# Lab4_schematic.net
KiCad netlist of a schematic drawn in EAGLE
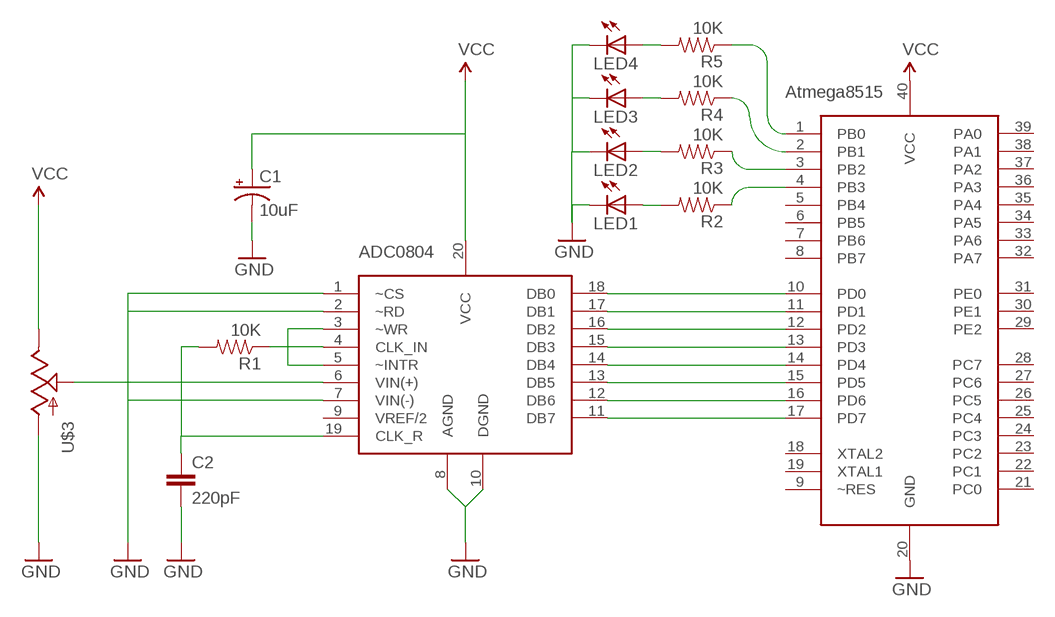
[diagram p0: schematic, sheet 1]

(export (version "E")
  (design (tool "Eeschema 10.0.6"))
  (components
    (comp (ref "C1")
      (value "10uF")
      (footprint "eagle-import:EIA3216")
      (libsource (lib "eagle-import") (part "CAP_POL1206"))
    )
    (comp (ref "C2")
      (value "220pF")
      (footprint "eagle-import:CAP-PTH-SMALL")
      (libsource (lib "eagle-import") (part "CAPPTH"))
    )
    (comp (ref "LED1")
      (value "LED3MM")
      (footprint "eagle-import:LED3MM")
      (libsource (lib "eagle-import") (part "LED3MM"))
    )
    (comp (ref "LED2")
      (value "LED3MM")
      (footprint "eagle-import:LED3MM")
      (libsource (lib "eagle-import") (part "LED3MM"))
    )
    (comp (ref "LED3")
      (value "LED3MM")
      (footprint "eagle-import:LED3MM")
      (libsource (lib "eagle-import") (part "LED3MM"))
    )
    (comp (ref "LED4")
      (value "LED3MM")
      (footprint "eagle-import:LED3MM")
      (libsource (lib "eagle-import") (part "LED3MM"))
    )
    (comp (ref "R1")
      (value "10K")
      (footprint "eagle-import:AXIAL-0.3")
      (libsource (lib "eagle-import") (part "RESISTORPTH1"))
    )
    (comp (ref "R2")
      (value "10K")
      (footprint "eagle-import:AXIAL-0.3")
      (libsource (lib "eagle-import") (part "RESISTORPTH1"))
    )
    (comp (ref "R3")
      (value "10K")
      (footprint "eagle-import:AXIAL-0.3")
      (libsource (lib "eagle-import") (part "RESISTORPTH1"))
    )
    (comp (ref "R4")
      (value "10K")
      (footprint "eagle-import:AXIAL-0.3")
      (libsource (lib "eagle-import") (part "RESISTORPTH1"))
    )
    (comp (ref "R5")
      (value "10K")
      (footprint "eagle-import:AXIAL-0.3")
      (libsource (lib "eagle-import") (part "RESISTORPTH1"))
    )
    (comp (ref "U$1")
      (value "ATMEGA8515")
      (footprint "eagle-import:DIL-40")
      (libsource (lib "eagle-import") (part "ATMEGA8515"))
    )
    (comp (ref "U$2")
      (value "ADC0804")
      (footprint "eagle-import:DIL20")
      (libsource (lib "eagle-import") (part "ADC0804"))
    )
    (comp (ref "U$3")
      (value "POT")
      (footprint "eagle-import:ALPS_POT")
      (libsource (lib "eagle-import") (part "POT"))
    )
  )
  (nets
    (net (code "1") (name "GND") (class "Default")
      (node (ref "C1") (pin "C") (pinfunction "-_C") (pintype "passive"))
      (node (ref "C2") (pin "2") (pinfunction "2_2") (pintype "passive"))
      (node (ref "LED1") (pin "K") (pinfunction "C_K") (pintype "passive"))
      (node (ref "LED2") (pin "K") (pinfunction "C_K") (pintype "passive"))
      (node (ref "LED3") (pin "K") (pinfunction "C_K") (pintype "passive"))
      (node (ref "LED4") (pin "K") (pinfunction "C_K") (pintype "passive"))
      (node (ref "U$1") (pin "20") (pinfunction "GND_20") (pintype "bidirectional"))
      (node (ref "U$2") (pin "1") (pinfunction "~{CS}_1") (pintype "bidirectional"))
      (node (ref "U$2") (pin "10") (pinfunction "DGND_10") (pintype "bidirectional"))
      (node (ref "U$2") (pin "2") (pinfunction "~{RD}_2") (pintype "bidirectional"))
      (node (ref "U$2") (pin "7") (pinfunction "VIN(-)_7") (pintype "bidirectional"))
      (node (ref "U$2") (pin "8") (pinfunction "AGND_8") (pintype "bidirectional"))
      (node (ref "U$3") (pin "P$3") (pinfunction "A_P$3") (pintype "passive"))
    )
    (net (code "2") (name "Net-(R1-1)") (class "Default")
      (node (ref "R1") (pin "P$1") (pinfunction "1_P$1") (pintype "passive"))
      (node (ref "U$2") (pin "4") (pinfunction "CLK_IN_4") (pintype "bidirectional"))
    )
    (net (code "3") (name "Net-(R1-2)") (class "Default")
      (node (ref "C2") (pin "1") (pinfunction "1_1") (pintype "passive"))
      (node (ref "R1") (pin "P$2") (pinfunction "2_P$2") (pintype "passive"))
      (node (ref "U$2") (pin "19") (pinfunction "CLK_R_19") (pintype "bidirectional"))
    )
    (net (code "4") (name "Net-(R2-1)") (class "Default")
      (node (ref "R2") (pin "P$1") (pinfunction "1_P$1") (pintype "passive"))
      (node (ref "U$1") (pin "4") (pinfunction "PB3_4") (pintype "bidirectional"))
    )
    (net (code "5") (name "Net-(R2-2)") (class "Default")
      (node (ref "LED1") (pin "A") (pinfunction "A_A") (pintype "passive"))
      (node (ref "R2") (pin "P$2") (pinfunction "2_P$2") (pintype "passive"))
    )
    (net (code "6") (name "Net-(R3-1)") (class "Default")
      (node (ref "R3") (pin "P$1") (pinfunction "1_P$1") (pintype "passive"))
      (node (ref "U$1") (pin "3") (pinfunction "PB2_3") (pintype "bidirectional"))
    )
    (net (code "7") (name "Net-(R3-2)") (class "Default")
      (node (ref "LED2") (pin "A") (pinfunction "A_A") (pintype "passive"))
      (node (ref "R3") (pin "P$2") (pinfunction "2_P$2") (pintype "passive"))
    )
    (net (code "8") (name "Net-(R4-1)") (class "Default")
      (node (ref "R4") (pin "P$1") (pinfunction "1_P$1") (pintype "passive"))
      (node (ref "U$1") (pin "2") (pinfunction "PB1_2") (pintype "bidirectional"))
    )
    (net (code "9") (name "Net-(R4-2)") (class "Default")
      (node (ref "LED3") (pin "A") (pinfunction "A_A") (pintype "passive"))
      (node (ref "R4") (pin "P$2") (pinfunction "2_P$2") (pintype "passive"))
    )
    (net (code "10") (name "Net-(R5-1)") (class "Default")
      (node (ref "R5") (pin "P$1") (pinfunction "1_P$1") (pintype "passive"))
      (node (ref "U$1") (pin "1") (pinfunction "PB0_1") (pintype "bidirectional"))
    )
    (net (code "11") (name "Net-(R5-2)") (class "Default")
      (node (ref "LED4") (pin "A") (pinfunction "A_A") (pintype "passive"))
      (node (ref "R5") (pin "P$2") (pinfunction "2_P$2") (pintype "passive"))
    )
    (net (code "12") (name "Net-(U$1-PD0)") (class "Default")
      (node (ref "U$1") (pin "10") (pinfunction "PD0_10") (pintype "bidirectional"))
      (node (ref "U$2") (pin "18") (pinfunction "DB0_18") (pintype "bidirectional"))
    )
    (net (code "13") (name "Net-(U$1-PD1)") (class "Default")
      (node (ref "U$1") (pin "11") (pinfunction "PD1_11") (pintype "bidirectional"))
      (node (ref "U$2") (pin "17") (pinfunction "DB1_17") (pintype "bidirectional"))
    )
    (net (code "14") (name "Net-(U$1-PD2)") (class "Default")
      (node (ref "U$1") (pin "12") (pinfunction "PD2_12") (pintype "bidirectional"))
      (node (ref "U$2") (pin "16") (pinfunction "DB2_16") (pintype "bidirectional"))
    )
    (net (code "15") (name "Net-(U$1-PD3)") (class "Default")
      (node (ref "U$1") (pin "13") (pinfunction "PD3_13") (pintype "bidirectional"))
      (node (ref "U$2") (pin "15") (pinfunction "DB3_15") (pintype "bidirectional"))
    )
    (net (code "16") (name "Net-(U$1-PD4)") (class "Default")
      (node (ref "U$1") (pin "14") (pinfunction "PD4_14") (pintype "bidirectional"))
      (node (ref "U$2") (pin "14") (pinfunction "DB4_14") (pintype "bidirectional"))
    )
    (net (code "17") (name "Net-(U$1-PD5)") (class "Default")
      (node (ref "U$1") (pin "15") (pinfunction "PD5_15") (pintype "bidirectional"))
      (node (ref "U$2") (pin "13") (pinfunction "DB5_13") (pintype "bidirectional"))
    )
    (net (code "18") (name "Net-(U$1-PD6)") (class "Default")
      (node (ref "U$1") (pin "16") (pinfunction "PD6_16") (pintype "bidirectional"))
      (node (ref "U$2") (pin "12") (pinfunction "DB6_12") (pintype "bidirectional"))
    )
    (net (code "19") (name "Net-(U$1-PD7)") (class "Default")
      (node (ref "U$1") (pin "17") (pinfunction "PD7_17") (pintype "bidirectional"))
      (node (ref "U$2") (pin "11") (pinfunction "DB7_11") (pintype "bidirectional"))
    )
    (net (code "20") (name "Net-(U$2-VIN(+))") (class "Default")
      (node (ref "U$2") (pin "6") (pinfunction "VIN(+)_6") (pintype "bidirectional"))
      (node (ref "U$3") (pin "P$2") (pinfunction "S_P$2") (pintype "passive"))
    )
    (net (code "21") (name "Net-(U$2-~{INTR})") (class "Default")
      (node (ref "U$2") (pin "3") (pinfunction "~{WR}_3") (pintype "bidirectional"))
      (node (ref "U$2") (pin "5") (pinfunction "~{INTR}_5") (pintype "bidirectional"))
    )
    (net (code "22") (name "VCC") (class "Default")
      (node (ref "C1") (pin "A") (pinfunction "+_A") (pintype "passive"))
      (node (ref "U$1") (pin "40") (pinfunction "VCC_40") (pintype "bidirectional"))
      (node (ref "U$2") (pin "20") (pinfunction "VCC_20") (pintype "bidirectional"))
      (node (ref "U$3") (pin "P$1") (pinfunction "E_P$1") (pintype "passive"))
    )
    (net (code "23") (name "unconnected-(U$1-PA0-Pad39)") (class "Default")
      (node (ref "U$1") (pin "39") (pinfunction "PA0_39") (pintype "bidirectional"))
    )
    (net (code "24") (name "unconnected-(U$1-PA1-Pad38)") (class "Default")
      (node (ref "U$1") (pin "38") (pinfunction "PA1_38") (pintype "bidirectional"))
    )
    (net (code "25") (name "unconnected-(U$1-PA2-Pad37)") (class "Default")
      (node (ref "U$1") (pin "37") (pinfunction "PA2_37") (pintype "bidirectional"))
    )
    (net (code "26") (name "unconnected-(U$1-PA3-Pad36)") (class "Default")
      (node (ref "U$1") (pin "36") (pinfunction "PA3_36") (pintype "bidirectional"))
    )
    (net (code "27") (name "unconnected-(U$1-PA4-Pad35)") (class "Default")
      (node (ref "U$1") (pin "35") (pinfunction "PA4_35") (pintype "bidirectional"))
    )
    (net (code "28") (name "unconnected-(U$1-PA5-Pad34)") (class "Default")
      (node (ref "U$1") (pin "34") (pinfunction "PA5_34") (pintype "bidirectional"))
    )
    (net (code "29") (name "unconnected-(U$1-PA6-Pad33)") (class "Default")
      (node (ref "U$1") (pin "33") (pinfunction "PA6_33") (pintype "bidirectional"))
    )
    (net (code "30") (name "unconnected-(U$1-PA7-Pad32)") (class "Default")
      (node (ref "U$1") (pin "32") (pinfunction "PA7_32") (pintype "bidirectional"))
    )
    (net (code "31") (name "unconnected-(U$1-PB4-Pad5)") (class "Default")
      (node (ref "U$1") (pin "5") (pinfunction "PB4_5") (pintype "bidirectional"))
    )
    (net (code "32") (name "unconnected-(U$1-PB5-Pad6)") (class "Default")
      (node (ref "U$1") (pin "6") (pinfunction "PB5_6") (pintype "bidirectional"))
    )
    (net (code "33") (name "unconnected-(U$1-PB6-Pad7)") (class "Default")
      (node (ref "U$1") (pin "7") (pinfunction "PB6_7") (pintype "bidirectional"))
    )
    (net (code "34") (name "unconnected-(U$1-PB7-Pad8)") (class "Default")
      (node (ref "U$1") (pin "8") (pinfunction "PB7_8") (pintype "bidirectional"))
    )
    (net (code "35") (name "unconnected-(U$1-PC0-Pad21)") (class "Default")
      (node (ref "U$1") (pin "21") (pinfunction "PC0_21") (pintype "bidirectional"))
    )
    (net (code "36") (name "unconnected-(U$1-PC1-Pad22)") (class "Default")
      (node (ref "U$1") (pin "22") (pinfunction "PC1_22") (pintype "bidirectional"))
    )
    (net (code "37") (name "unconnected-(U$1-PC2-Pad23)") (class "Default")
      (node (ref "U$1") (pin "23") (pinfunction "PC2_23") (pintype "bidirectional"))
    )
    (net (code "38") (name "unconnected-(U$1-PC3-Pad24)") (class "Default")
      (node (ref "U$1") (pin "24") (pinfunction "PC3_24") (pintype "bidirectional"))
    )
    (net (code "39") (name "unconnected-(U$1-PC4-Pad25)") (class "Default")
      (node (ref "U$1") (pin "25") (pinfunction "PC4_25") (pintype "bidirectional"))
    )
    (net (code "40") (name "unconnected-(U$1-PC5-Pad26)") (class "Default")
      (node (ref "U$1") (pin "26") (pinfunction "PC5_26") (pintype "bidirectional"))
    )
    (net (code "41") (name "unconnected-(U$1-PC6-Pad27)") (class "Default")
      (node (ref "U$1") (pin "27") (pinfunction "PC6_27") (pintype "bidirectional"))
    )
    (net (code "42") (name "unconnected-(U$1-PC7-Pad28)") (class "Default")
      (node (ref "U$1") (pin "28") (pinfunction "PC7_28") (pintype "bidirectional"))
    )
    (net (code "43") (name "unconnected-(U$1-PE0-Pad31)") (class "Default")
      (node (ref "U$1") (pin "31") (pinfunction "PE0_31") (pintype "bidirectional"))
    )
    (net (code "44") (name "unconnected-(U$1-PE1-Pad30)") (class "Default")
      (node (ref "U$1") (pin "30") (pinfunction "PE1_30") (pintype "bidirectional"))
    )
    (net (code "45") (name "unconnected-(U$1-PE2-Pad29)") (class "Default")
      (node (ref "U$1") (pin "29") (pinfunction "PE2_29") (pintype "bidirectional"))
    )
    (net (code "46") (name "unconnected-(U$1-XTAL1-Pad19)") (class "Default")
      (node (ref "U$1") (pin "19") (pinfunction "XTAL1_19") (pintype "bidirectional"))
    )
    (net (code "47") (name "unconnected-(U$1-XTAL2-Pad18)") (class "Default")
      (node (ref "U$1") (pin "18") (pinfunction "XTAL2_18") (pintype "bidirectional"))
    )
    (net (code "48") (name "unconnected-(U$1-~{RES}-Pad9)") (class "Default")
      (node (ref "U$1") (pin "9") (pinfunction "~{RES}_9") (pintype "bidirectional"))
    )
    (net (code "49") (name "unconnected-(U$2-VREF{slash}2-Pad9)") (class "Default")
      (node (ref "U$2") (pin "9") (pinfunction "VREF/2_9") (pintype "bidirectional"))
    )
  )
)
